# prototype2-whole-through-usb.net
KiCad netlist of a schematic drawn in EAGLE
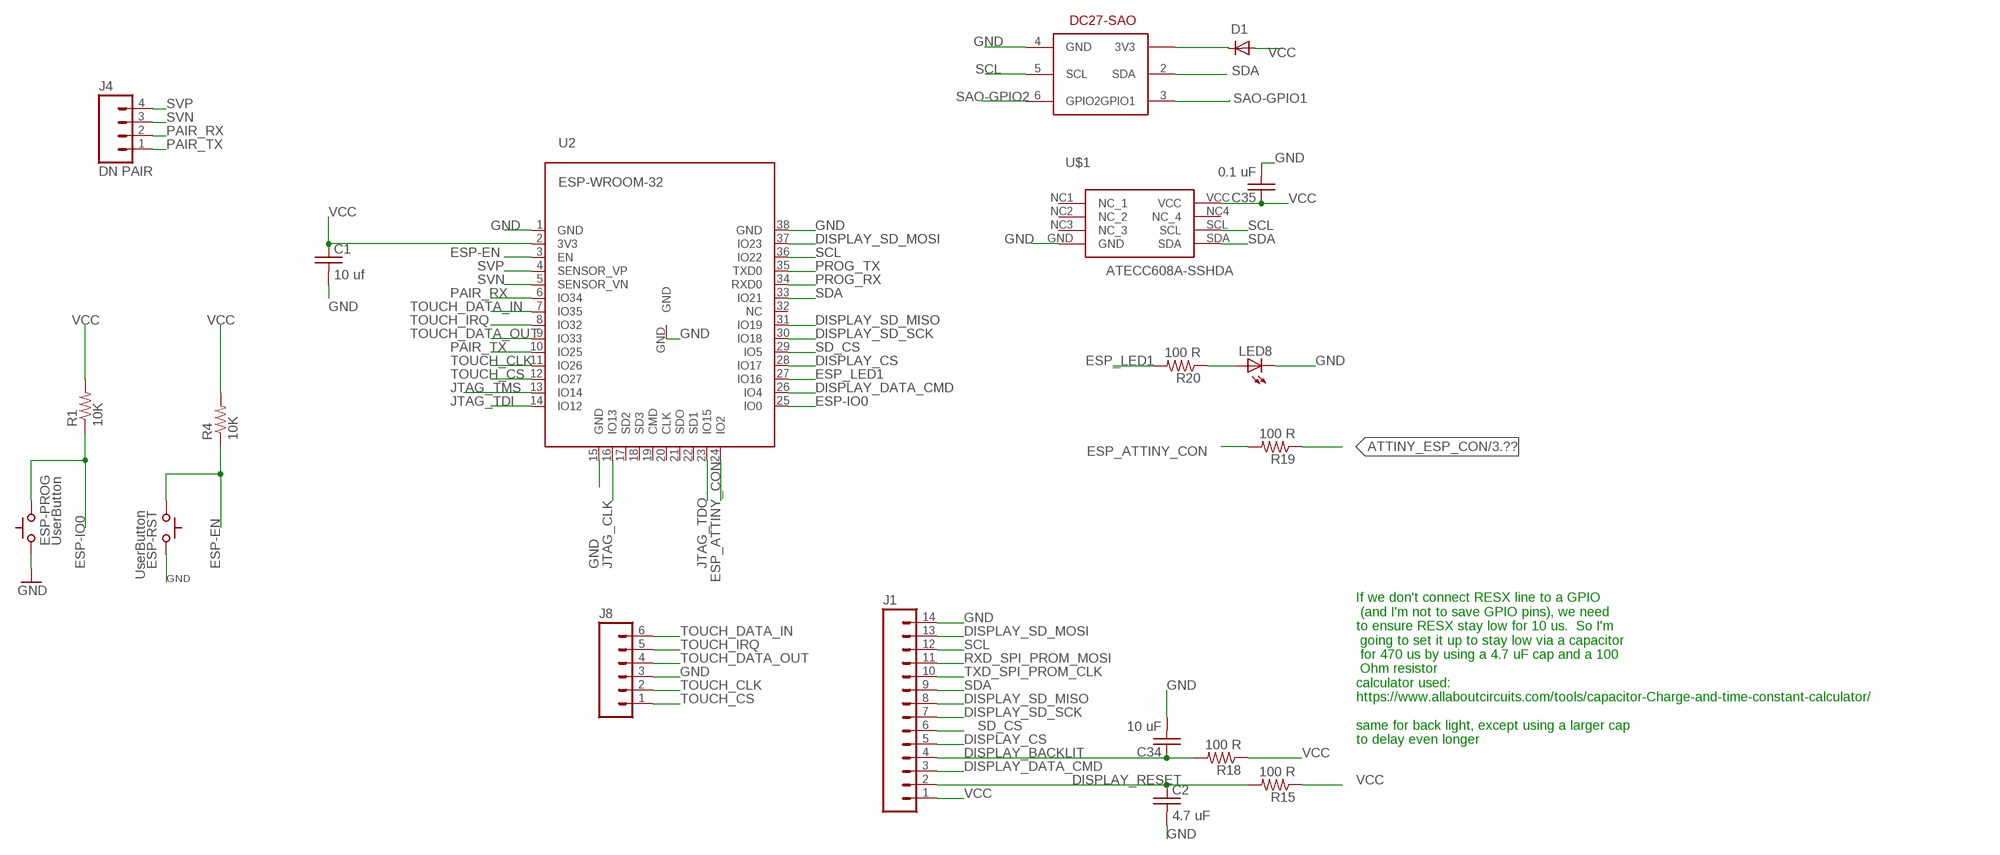
[diagram p0: schematic, sheet 1]
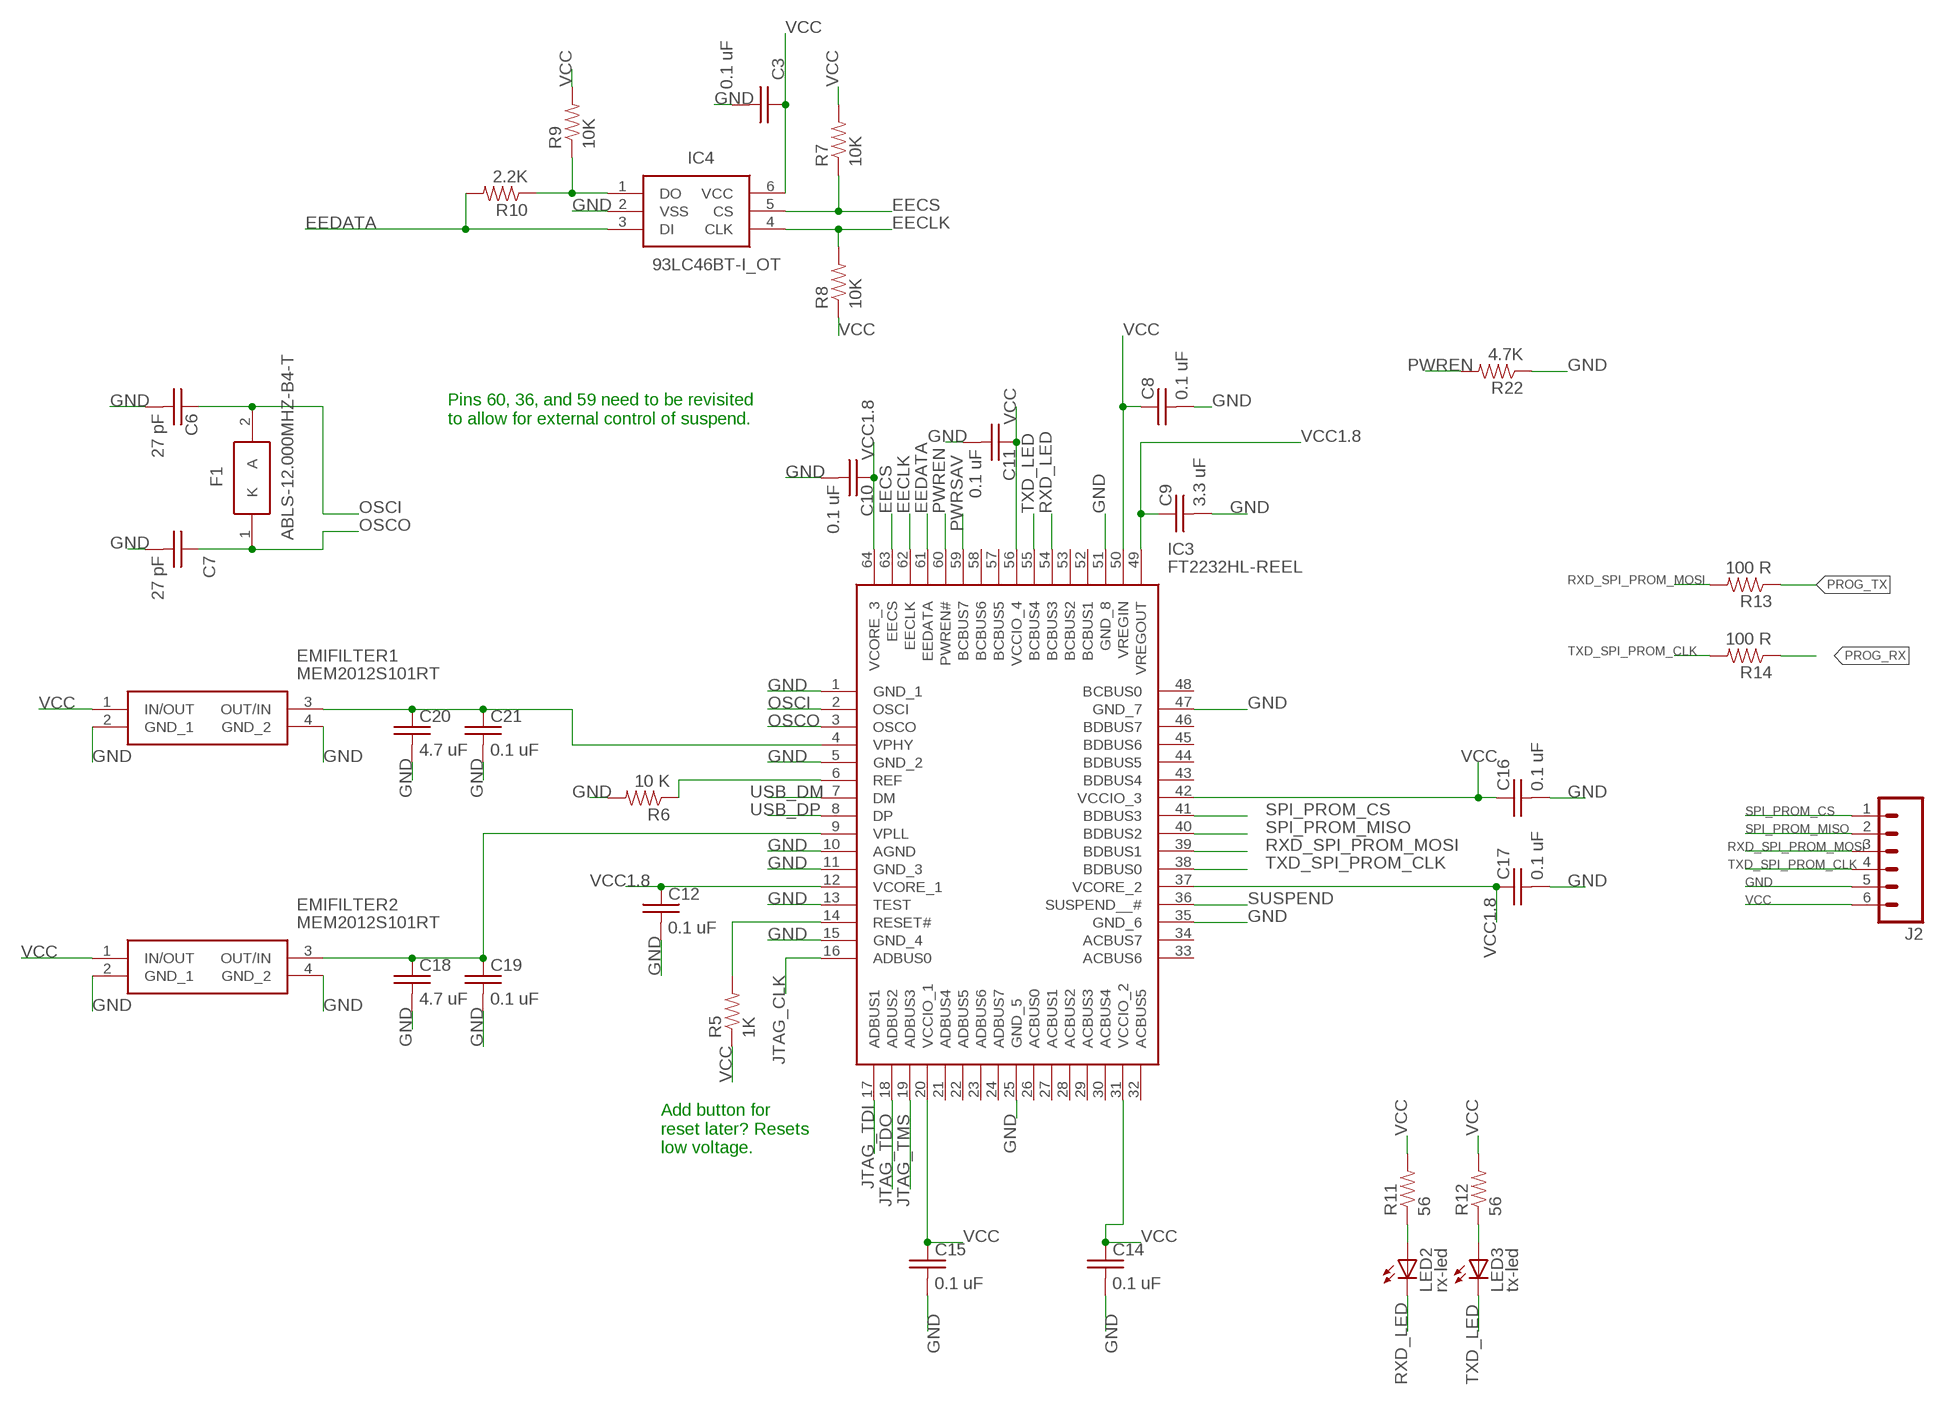
[diagram p1: schematic, sheet 2]
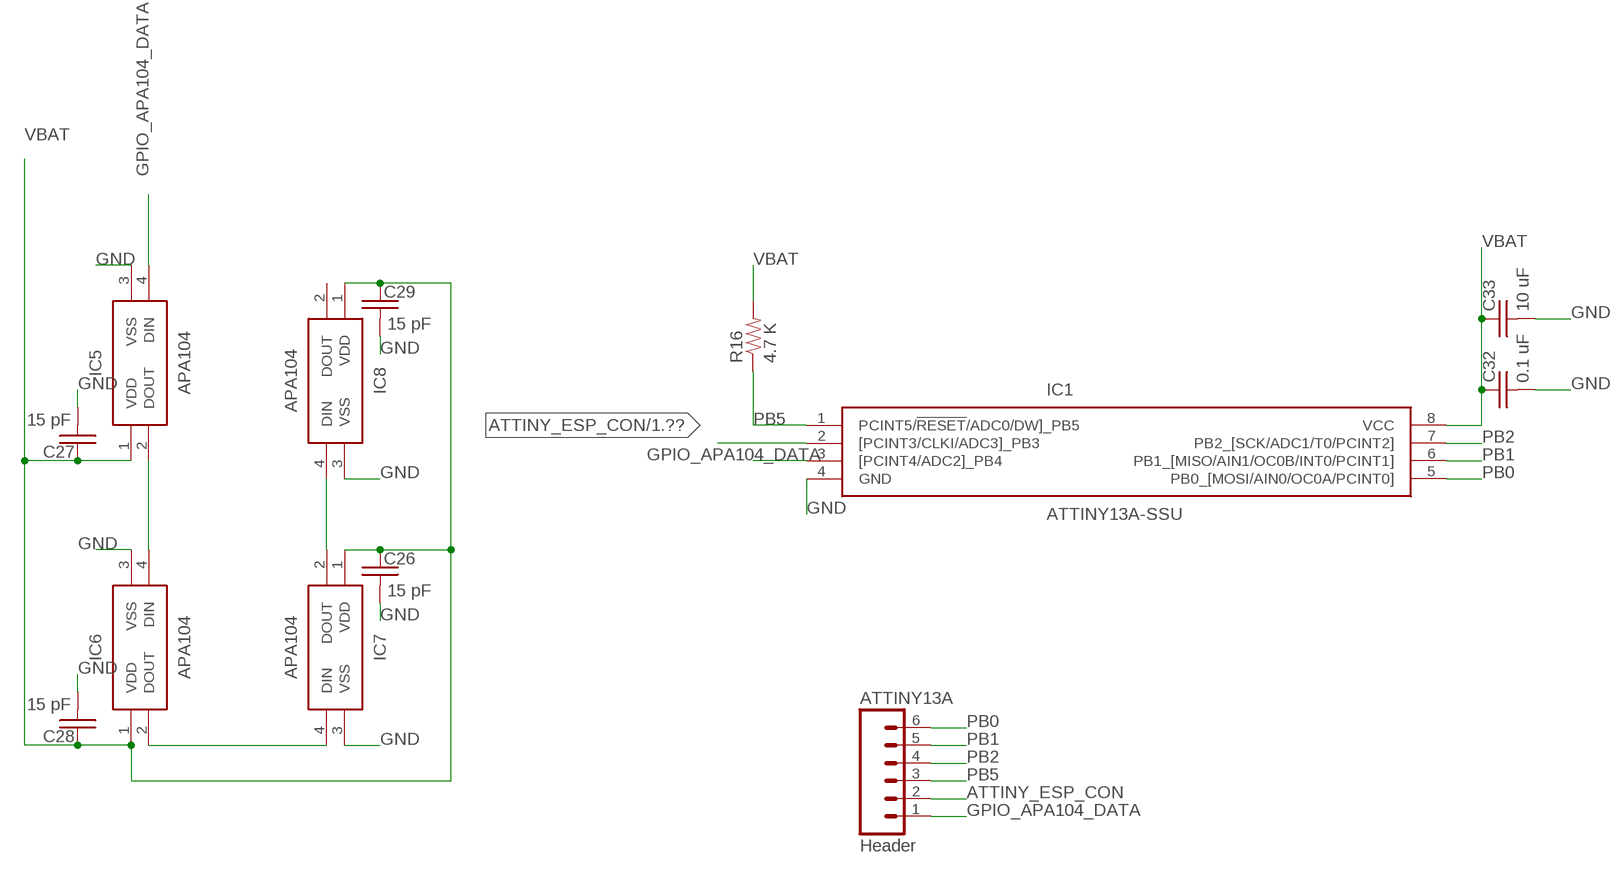
[diagram p2: schematic, sheet 3]
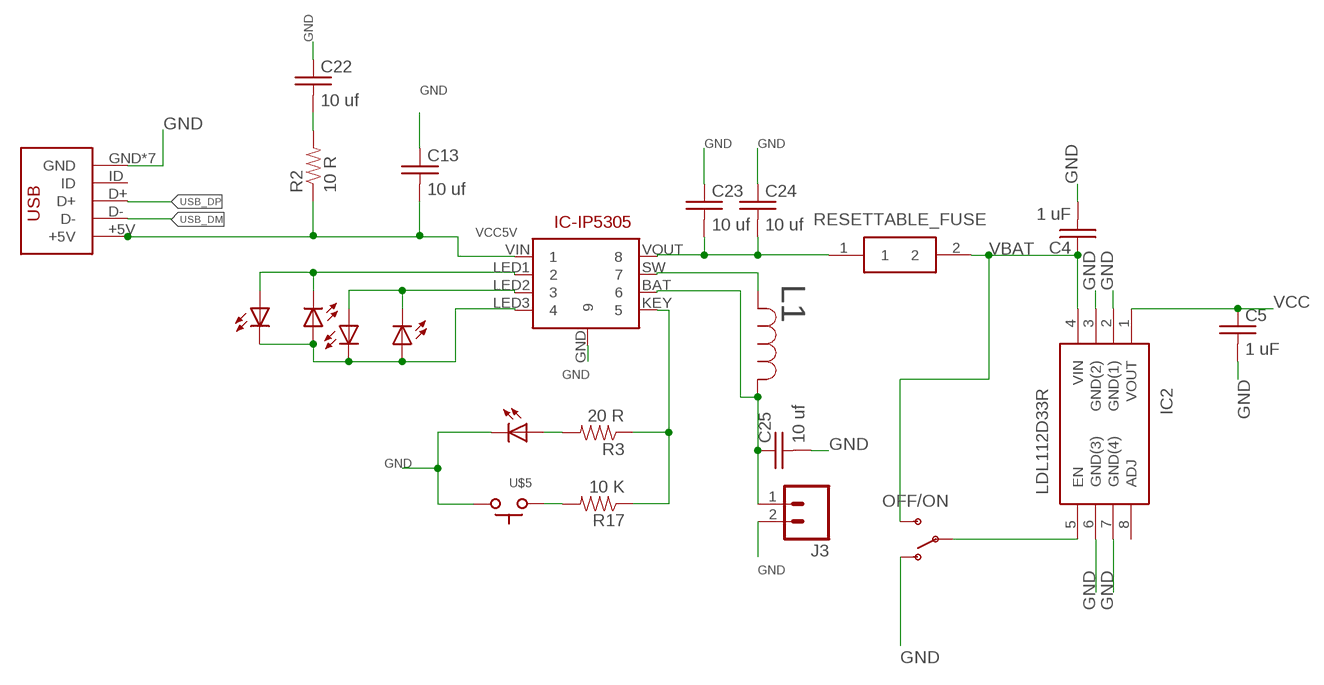
[diagram p3: schematic, sheet 4]
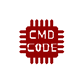
[diagram p4: schematic, sheet 5]

(export (version "E")
  (design (tool "Eeschema 10.0.6"))
  (components
    (comp (ref "ATTINY13A")
      (value "Header")
      (footprint "eagle-import:1X06")
      (libsource (lib "eagle-import") (part "M06SILK_FEMALE_PTH"))
    )
    (comp (ref "C26")
      (value "15 pF")
      (footprint "eagle-import:C0805")
      (libsource (lib "eagle-import") (part "C-USC0805"))
    )
    (comp (ref "C27")
      (value "15 pF")
      (footprint "eagle-import:C0805")
      (libsource (lib "eagle-import") (part "C-USC0805"))
    )
    (comp (ref "C28")
      (value "15 pF")
      (footprint "eagle-import:C0805")
      (libsource (lib "eagle-import") (part "C-USC0805"))
    )
    (comp (ref "C29")
      (value "15 pF")
      (footprint "eagle-import:C0805")
      (libsource (lib "eagle-import") (part "C-USC0805"))
    )
    (comp (ref "C32")
      (value "0.1 uF")
      (footprint "eagle-import:C0805")
      (libsource (lib "eagle-import") (part "C-USC0805"))
    )
    (comp (ref "C33")
      (value "10 uF")
      (footprint "eagle-import:C0805")
      (libsource (lib "eagle-import") (part "C-USC0805"))
    )
    (comp (ref "IC1")
      (value "ATTINY13A-SSU")
      (footprint "eagle-import:SOIC127P600X175-8N")
      (fields (field (name "MOUSER_PART_NUMBER") "556-ATTINY13A-SSU"))
      (libsource (lib "eagle-import") (part "ATTINY13A-SSU"))
    )
    (comp (ref "IC5")
      (value "APA104")
      (footprint "eagle-import:APA104")
      (libsource (lib "eagle-import") (part "APA104"))
    )
    (comp (ref "IC6")
      (value "APA104")
      (footprint "eagle-import:APA104")
      (libsource (lib "eagle-import") (part "APA104"))
    )
    (comp (ref "IC7")
      (value "APA104")
      (footprint "eagle-import:APA104")
      (libsource (lib "eagle-import") (part "APA104"))
    )
    (comp (ref "IC8")
      (value "APA104")
      (footprint "eagle-import:APA104")
      (libsource (lib "eagle-import") (part "APA104"))
    )
    (comp (ref "R16")
      (value "4.7 K")
      (footprint "eagle-import:0805")
      (libsource (lib "eagle-import") (part "passives_RESISTOR0805-RES"))
    )
    (comp (ref "C1")
      (value "10 uf")
      (footprint "eagle-import:C0805")
      (libsource (lib "eagle-import") (part "C-USC0805"))
    )
    (comp (ref "C2")
      (value "4.7 uF")
      (footprint "eagle-import:C0805")
      (libsource (lib "eagle-import") (part "C-USC0805"))
    )
    (comp (ref "C34")
      (value "10 uF")
      (footprint "eagle-import:C0805")
      (libsource (lib "eagle-import") (part "C-USC0805"))
    )
    (comp (ref "C35")
      (value "0.1 uF")
      (footprint "eagle-import:C0805")
      (libsource (lib "eagle-import") (part "C-USC0805"))
    )
    (comp (ref "D1")
      (value "DIODESMA")
      (footprint "eagle-import:SMA-DIODE")
      (libsource (lib "eagle-import") (part "DIODESMA"))
    )
    (comp (ref "ESP-PROG")
      (value "UserButton")
      (footprint "eagle-import:TACTILE-2PIN-NARROW")
      (libsource (lib "eagle-import") (part "SWITCH_TACTILETACTILE-2PIN-NARROW"))
    )
    (comp (ref "ESP-RST")
      (value "UserButton")
      (footprint "eagle-import:TACTILE-2PIN-NARROW")
      (libsource (lib "eagle-import") (part "SWITCH_TACTILETACTILE-2PIN-NARROW"))
    )
    (comp (ref "J1")
      (value "M14")
      (footprint "eagle-import:1X14")
      (libsource (lib "eagle-import") (part "M14"))
    )
    (comp (ref "J4")
      (value "DN PAIR")
      (footprint "eagle-import:1X04")
      (libsource (lib "eagle-import") (part "M04PTH"))
    )
    (comp (ref "J8")
      (value "M06NO_SILK_YES_STOP")
      (footprint "eagle-import:1X06_NO_SILK_YES_STOP")
      (libsource (lib "eagle-import") (part "M06NO_SILK_YES_STOP"))
    )
    (comp (ref "LED8")
      (value "LED3MM")
      (footprint "eagle-import:LED3MM")
      (libsource (lib "eagle-import") (part "LED3MM"))
    )
    (comp (ref "R1")
      (value "10K")
      (footprint "eagle-import:0805")
      (libsource (lib "eagle-import") (part "RESISTOR0805-RES"))
    )
    (comp (ref "R4")
      (value "10K")
      (footprint "eagle-import:0805")
      (libsource (lib "eagle-import") (part "RESISTOR0805-RES"))
    )
    (comp (ref "R15")
      (value "100 R")
      (footprint "eagle-import:0805")
      (libsource (lib "eagle-import") (part "RESISTOR0805-RES"))
    )
    (comp (ref "R18")
      (value "100 R")
      (footprint "eagle-import:0805")
      (libsource (lib "eagle-import") (part "RESISTOR0805-RES"))
    )
    (comp (ref "R19")
      (value "100 R")
      (footprint "eagle-import:0805")
      (libsource (lib "eagle-import") (part "RESISTOR0805-RES"))
    )
    (comp (ref "R20")
      (value "100 R")
      (footprint "eagle-import:0805")
      (libsource (lib "eagle-import") (part "RESISTOR0805-RES"))
    )
    (comp (ref "U$1")
      (value "ATECC608A-SSHDA")
      (footprint "eagle-import:8-SOIC")
      (libsource (lib "eagle-import") (part "ATECC608A-SSHDA"))
    )
    (comp (ref "U$4")
      (value "DC-27-SAO")
      (footprint "eagle-import:3X2")
      (libsource (lib "eagle-import") (part "DC-27-SAO"))
    )
    (comp (ref "U2")
      (value "ESP-WROOM-32")
      (footprint "eagle-import:ESP-WROOM-32")
      (libsource (lib "eagle-import") (part "ESP-WROOM-32"))
    )
    (comp (ref "C3")
      (value "0.1 uF")
      (footprint "eagle-import:C0805")
      (libsource (lib "eagle-import") (part "C-USC0805"))
    )
    (comp (ref "C6")
      (value "27 pF")
      (footprint "eagle-import:C0805")
      (libsource (lib "eagle-import") (part "C-USC0805"))
    )
    (comp (ref "C7")
      (value "27 pF")
      (footprint "eagle-import:C0805")
      (libsource (lib "eagle-import") (part "C-USC0805"))
    )
    (comp (ref "C8")
      (value "0.1 uF")
      (footprint "eagle-import:C0805")
      (libsource (lib "eagle-import") (part "C-USC0805"))
    )
    (comp (ref "C9")
      (value "3.3 uF")
      (footprint "eagle-import:C0805")
      (libsource (lib "eagle-import") (part "C-USC0805"))
    )
    (comp (ref "C10")
      (value "0.1 uF")
      (footprint "eagle-import:C0805")
      (libsource (lib "eagle-import") (part "C-USC0805"))
    )
    (comp (ref "C11")
      (value "0.1 uF")
      (footprint "eagle-import:C0805")
      (libsource (lib "eagle-import") (part "C-USC0805"))
    )
    (comp (ref "C12")
      (value "0.1 uF")
      (footprint "eagle-import:C0805")
      (libsource (lib "eagle-import") (part "C-USC0805"))
    )
    (comp (ref "C14")
      (value "0.1 uF")
      (footprint "eagle-import:C0805")
      (libsource (lib "eagle-import") (part "C-USC0805"))
    )
    (comp (ref "C15")
      (value "0.1 uF")
      (footprint "eagle-import:C0805")
      (libsource (lib "eagle-import") (part "C-USC0805"))
    )
    (comp (ref "C16")
      (value "0.1 uF")
      (footprint "eagle-import:C0805")
      (libsource (lib "eagle-import") (part "C-USC0805"))
    )
    (comp (ref "C17")
      (value "0.1 uF")
      (footprint "eagle-import:C0805")
      (libsource (lib "eagle-import") (part "C-USC0805"))
    )
    (comp (ref "C18")
      (value "4.7 uF")
      (footprint "eagle-import:C0805")
      (libsource (lib "eagle-import") (part "C-USC0805"))
    )
    (comp (ref "C19")
      (value "0.1 uF")
      (footprint "eagle-import:C0805")
      (libsource (lib "eagle-import") (part "C-USC0805"))
    )
    (comp (ref "C20")
      (value "4.7 uF")
      (footprint "eagle-import:C0805")
      (libsource (lib "eagle-import") (part "C-USC0805"))
    )
    (comp (ref "C21")
      (value "0.1 uF")
      (footprint "eagle-import:C0805")
      (libsource (lib "eagle-import") (part "C-USC0805"))
    )
    (comp (ref "EMIFILTER1")
      (value "MEM2012S101RT")
      (footprint "eagle-import:MEM2012S101RT")
      (libsource (lib "eagle-import") (part "MEM2012S101RT"))
    )
    (comp (ref "EMIFILTER2")
      (value "MEM2012S101RT")
      (footprint "eagle-import:MEM2012S101RT")
      (libsource (lib "eagle-import") (part "MEM2012S101RT"))
    )
    (comp (ref "F1")
      (value "ABLS-12.000MHZ-B4-T")
      (footprint "eagle-import:HC_49US-(AT49)_1")
      (fields
        (field (name "MOUSER_PART_NUMBER") "815-ABLS-12.0M-T")
        (field (name "RS_PART_NUMBER") "1710207")
      )
      (libsource (lib "eagle-import") (part "ABLS-12.000MHZ-B4-T"))
    )
    (comp (ref "IC3")
      (value "FT2232HL-REEL")
      (footprint "eagle-import:QFP50P1200X1200X160-64N")
      (fields (field (name "MOUSER_PART_NUMBER") "895-FT2232HL"))
      (libsource (lib "eagle-import") (part "FT2232HL-REEL"))
    )
    (comp (ref "IC4")
      (value "93LC46BT-I_OT")
      (footprint "eagle-import:SOT95P270X145-6N")
      (fields
        (field (name "MANUFACTURER_PART_NUMBER") "93LC46BT-I/OT")
        (field (name "MOUSER_PART_NUMBER") "579-93LC46BT-I/OT")
      )
      (libsource (lib "eagle-import") (part "93LC46BT-I_OT"))
    )
    (comp (ref "J2")
      (value "M06SILK_FEMALE_PTH")
      (footprint "eagle-import:1X06")
      (libsource (lib "eagle-import") (part "M06SILK_FEMALE_PTH"))
    )
    (comp (ref "LED2")
      (value "rx-led")
      (footprint "eagle-import:LED3MM")
      (libsource (lib "eagle-import") (part "LED3MM"))
    )
    (comp (ref "LED3")
      (value "tx-led")
      (footprint "eagle-import:LED3MM")
      (libsource (lib "eagle-import") (part "LED3MM"))
    )
    (comp (ref "R5")
      (value "1K")
      (footprint "eagle-import:0805")
      (libsource (lib "eagle-import") (part "passives_RESISTOR0805-RES"))
    )
    (comp (ref "R6")
      (value "10 K")
      (footprint "eagle-import:0805")
      (libsource (lib "eagle-import") (part "passives_RESISTOR0805-RES"))
    )
    (comp (ref "R7")
      (value "10K")
      (footprint "eagle-import:0805")
      (libsource (lib "eagle-import") (part "passives_RESISTOR0805-RES"))
    )
    (comp (ref "R8")
      (value "10K")
      (footprint "eagle-import:0805")
      (libsource (lib "eagle-import") (part "passives_RESISTOR0805-RES"))
    )
    (comp (ref "R9")
      (value "10K")
      (footprint "eagle-import:0805")
      (libsource (lib "eagle-import") (part "passives_RESISTOR0805-RES"))
    )
    (comp (ref "R10")
      (value "2.2K")
      (footprint "eagle-import:0805")
      (libsource (lib "eagle-import") (part "passives_RESISTOR0805-RES"))
    )
    (comp (ref "R11")
      (value "56")
      (footprint "eagle-import:0805")
      (libsource (lib "eagle-import") (part "passives_RESISTOR0805-RES"))
    )
    (comp (ref "R12")
      (value "56")
      (footprint "eagle-import:0805")
      (libsource (lib "eagle-import") (part "passives_RESISTOR0805-RES"))
    )
    (comp (ref "R13")
      (value "100 R")
      (footprint "eagle-import:0805")
      (libsource (lib "eagle-import") (part "passives_RESISTOR0805-RES"))
    )
    (comp (ref "R14")
      (value "100 R")
      (footprint "eagle-import:0805")
      (libsource (lib "eagle-import") (part "passives_RESISTOR0805-RES"))
    )
    (comp (ref "R22")
      (value "4.7K")
      (footprint "eagle-import:0805")
      (libsource (lib "eagle-import") (part "passives_RESISTOR0805-RES"))
    )
    (comp (ref "C4")
      (value "1 uF")
      (footprint "eagle-import:C0805")
      (libsource (lib "eagle-import") (part "C-USC0805"))
    )
    (comp (ref "C5")
      (value "1 uF")
      (footprint "eagle-import:C0805")
      (libsource (lib "eagle-import") (part "C-USC0805"))
    )
    (comp (ref "C13")
      (value "10 uf")
      (footprint "eagle-import:C0805")
      (libsource (lib "eagle-import") (part "C-USC0805"))
    )
    (comp (ref "C22")
      (value "10 uf")
      (footprint "eagle-import:C0805")
      (libsource (lib "eagle-import") (part "C-USC0805"))
    )
    (comp (ref "C23")
      (value "10 uf")
      (footprint "eagle-import:C0805")
      (libsource (lib "eagle-import") (part "C-USC0805"))
    )
    (comp (ref "C24")
      (value "10 uf")
      (footprint "eagle-import:C0805")
      (libsource (lib "eagle-import") (part "C-USC0805"))
    )
    (comp (ref "C25")
      (value "10 uf")
      (footprint "eagle-import:C0805")
      (libsource (lib "eagle-import") (part "C-USC0805"))
    )
    (comp (ref "IC-IP5305")
      (value "IP5305ESOP8")
      (footprint "eagle-import:SOIC127P600X165-8")
      (libsource (lib "eagle-import") (part "IP5305ESOP8"))
    )
    (comp (ref "IC2")
      (value "LDL112D33R")
      (footprint "eagle-import:SOIC127P600X175-8N")
      (libsource (lib "eagle-import") (part "LDL112D33R"))
    )
    (comp (ref "J3")
      (value "M02PTH")
      (footprint "eagle-import:1X02")
      (libsource (lib "eagle-import") (part "M02PTH"))
    )
    (comp (ref "L1")
      (value "NRS4018T2R2MDGJ")
      (footprint "eagle-import:IND_TAIYO_NRS4018")
      (libsource (lib "eagle-import") (part "NRS4018T2R2MDGJ"))
    )
    (comp (ref "LED1")
      (value "LED3MM")
      (footprint "eagle-import:LED3MM")
      (libsource (lib "eagle-import") (part "LED3MM"))
    )
    (comp (ref "LED4")
      (value "LED3MM")
      (footprint "eagle-import:LED3MM")
      (libsource (lib "eagle-import") (part "LED3MM"))
    )
    (comp (ref "LED5")
      (value "LED3MM")
      (footprint "eagle-import:LED3MM")
      (libsource (lib "eagle-import") (part "LED3MM"))
    )
    (comp (ref "LED6")
      (value "LED3MM")
      (footprint "eagle-import:LED3MM")
      (libsource (lib "eagle-import") (part "LED3MM"))
    )
    (comp (ref "LED7")
      (value "LED3MM")
      (footprint "eagle-import:LED3MM")
      (libsource (lib "eagle-import") (part "LED3MM"))
    )
    (comp (ref "OFF/ON")
      (value "SWITCH-SPSTKIT")
      (footprint "eagle-import:SWITCH-SPDT_KIT")
      (libsource (lib "eagle-import") (part "SWITCH-SPSTKIT"))
    )
    (comp (ref "R2")
      (value "10 R")
      (footprint "eagle-import:0805")
      (libsource (lib "eagle-import") (part "passives_RESISTOR0805-RES"))
    )
    (comp (ref "R3")
      (value "20 R")
      (footprint "eagle-import:0805")
      (libsource (lib "eagle-import") (part "passives_RESISTOR0805-RES"))
    )
    (comp (ref "R17")
      (value "10 K")
      (footprint "eagle-import:0805")
      (libsource (lib "eagle-import") (part "passives_RESISTOR0805-RES"))
    )
    (comp (ref "RESETTABLE_FUSE")
      (value "0ZCJ0050FF2G")
      (footprint "eagle-import:FUSC3216X55N")
      (libsource (lib "eagle-import") (part "0ZCJ0050FF2G"))
    )
    (comp (ref "U$2")
      (value "DX4R005JJ2DX4R005JJ2")
      (footprint "eagle-import:DX4R005JJ2")
      (libsource (lib "eagle-import") (part "DX4R005JJ2DX4R005JJ2"))
    )
    (comp (ref "U$5")
      (value "SWITCH_TACTILETACTILE-2PIN-NARROW")
      (footprint "eagle-import:TACTILE-2PIN-NARROW")
      (libsource (lib "eagle-import") (part "switches_SWITCH_TACTILETACTILE-2PIN-NARROW"))
    )
    (comp (ref "U$3")
      (value "CMD_C0DE_LOGOCMD_CODE_LOGO_TOP_COPPER")
      (footprint "eagle-import:CMD_C0DE_LOGO_TOP_COPPER")
      (libsource (lib "eagle-import") (part "CMD_C0DE_LOGOCMD_CODE_LOGO_TOP_COPPER"))
    )
  )
  (nets
    (net (code "1") (name "ATTINY_ESP_CON") (class "Default")
      (node (ref "ATTINY13A") (pin "2") (pinfunction "2_2") (pintype "passive"))
      (node (ref "IC1") (pin "2") (pinfunction "[PCINT3/CLKI/ADC3]_PB3_2") (pintype "input"))
      (node (ref "R19") (pin "1") (pinfunction "1_1") (pintype "passive"))
    )
    (net (code "2") (name "DISPLAY_BACKLIT") (class "Default")
      (node (ref "C34") (pin "1") (pinfunction "1_1") (pintype "passive"))
      (node (ref "J1") (pin "4") (pinfunction "4_4") (pintype "passive"))
      (node (ref "R18") (pin "2") (pinfunction "2_2") (pintype "passive"))
    )
    (net (code "3") (name "DISPLAY_CS") (class "Default")
      (node (ref "J1") (pin "5") (pinfunction "5_5") (pintype "passive"))
      (node (ref "U2") (pin "28") (pinfunction "IO17_28") (pintype "bidirectional"))
    )
    (net (code "4") (name "DISPLAY_DATA_CMD") (class "Default")
      (node (ref "J1") (pin "3") (pinfunction "3_3") (pintype "passive"))
      (node (ref "U2") (pin "26") (pinfunction "IO4_26") (pintype "bidirectional"))
    )
    (net (code "5") (name "DISPLAY_RESET") (class "Default")
      (node (ref "C2") (pin "1") (pinfunction "1_1") (pintype "passive"))
      (node (ref "J1") (pin "2") (pinfunction "2_2") (pintype "passive"))
      (node (ref "R15") (pin "2") (pinfunction "2_2") (pintype "passive"))
    )
    (net (code "6") (name "DISPLAY_SD_MISO") (class "Default")
      (node (ref "J1") (pin "8") (pinfunction "8_8") (pintype "passive"))
      (node (ref "U2") (pin "31") (pinfunction "IO19_31") (pintype "bidirectional"))
    )
    (net (code "7") (name "DISPLAY_SD_MOSI") (class "Default")
      (node (ref "J1") (pin "13") (pinfunction "13_13") (pintype "passive"))
      (node (ref "U2") (pin "37") (pinfunction "IO23_37") (pintype "bidirectional"))
    )
    (net (code "8") (name "DISPLAY_SD_SCK") (class "Default")
      (node (ref "J1") (pin "7") (pinfunction "7_7") (pintype "passive"))
      (node (ref "U2") (pin "30") (pinfunction "IO18_30") (pintype "bidirectional"))
    )
    (net (code "9") (name "EECLK") (class "Default")
      (node (ref "IC3") (pin "62") (pinfunction "EECLK_62") (pintype "bidirectional"))
      (node (ref "IC4") (pin "4") (pinfunction "CLK_4") (pintype "input"))
      (node (ref "R8") (pin "2") (pinfunction "2_2") (pintype "passive"))
    )
    (net (code "10") (name "EECS") (class "Default")
      (node (ref "IC3") (pin "63") (pinfunction "EECS_63") (pintype "bidirectional"))
      (node (ref "IC4") (pin "5") (pinfunction "CS_5") (pintype "input"))
      (node (ref "R7") (pin "1") (pinfunction "1_1") (pintype "passive"))
    )
    (net (code "11") (name "EEDATA") (class "Default")
      (node (ref "IC3") (pin "61") (pinfunction "EEDATA_61") (pintype "bidirectional"))
      (node (ref "IC4") (pin "3") (pinfunction "DI_3") (pintype "bidirectional"))
      (node (ref "R10") (pin "2") (pinfunction "2_2") (pintype "passive"))
    )
    (net (code "12") (name "ESP-EN") (class "Default")
      (node (ref "ESP-RST") (pin "P$2") (pinfunction "C_P$2") (pintype "passive"))
      (node (ref "R4") (pin "1") (pinfunction "1_1") (pintype "passive"))
      (node (ref "U2") (pin "3") (pinfunction "EN_3") (pintype "bidirectional"))
    )
    (net (code "13") (name "ESP-IO0") (class "Default")
      (node (ref "ESP-PROG") (pin "P$1") (pinfunction "A_P$1") (pintype "passive"))
      (node (ref "R1") (pin "1") (pinfunction "1_1") (pintype "passive"))
      (node (ref "U2") (pin "25") (pinfunction "IO0_25") (pintype "bidirectional"))
    )
    (net (code "14") (name "ESP_ATTINY_CON") (class "Default")
      (node (ref "R19") (pin "2") (pinfunction "2_2") (pintype "passive"))
      (node (ref "U2") (pin "24") (pinfunction "IO2_24") (pintype "bidirectional"))
    )
    (net (code "15") (name "ESP_LED1") (class "Default")
      (node (ref "R20") (pin "2") (pinfunction "2_2") (pintype "passive"))
      (node (ref "U2") (pin "27") (pinfunction "IO16_27") (pintype "bidirectional"))
    )
    (net (code "16") (name "GND") (class "Default")
      (node (ref "C1") (pin "2") (pinfunction "2_2") (pintype "passive"))
      (node (ref "C10") (pin "2") (pinfunction "2_2") (pintype "passive"))
      (node (ref "C11") (pin "2") (pinfunction "2_2") (pintype "passive"))
      (node (ref "C12") (pin "2") (pinfunction "2_2") (pintype "passive"))
      (node (ref "C13") (pin "1") (pinfunction "1_1") (pintype "passive"))
      (node (ref "C14") (pin "2") (pinfunction "2_2") (pintype "passive"))
      (node (ref "C15") (pin "2") (pinfunction "2_2") (pintype "passive"))
      (node (ref "C16") (pin "2") (pinfunction "2_2") (pintype "passive"))
      (node (ref "C17") (pin "2") (pinfunction "2_2") (pintype "passive"))
      (node (ref "C18") (pin "2") (pinfunction "2_2") (pintype "passive"))
      (node (ref "C19") (pin "2") (pinfunction "2_2") (pintype "passive"))
      (node (ref "C2") (pin "2") (pinfunction "2_2") (pintype "passive"))
      (node (ref "C20") (pin "2") (pinfunction "2_2") (pintype "passive"))
      (node (ref "C21") (pin "2") (pinfunction "2_2") (pintype "passive"))
      (node (ref "C22") (pin "1") (pinfunction "1_1") (pintype "passive"))
      (node (ref "C23") (pin "1") (pinfunction "1_1") (pintype "passive"))
      (node (ref "C24") (pin "1") (pinfunction "1_1") (pintype "passive"))
      (node (ref "C25") (pin "2") (pinfunction "2_2") (pintype "passive"))
      (node (ref "C26") (pin "2") (pinfunction "2_2") (pintype "passive"))
      (node (ref "C27") (pin "2") (pinfunction "2_2") (pintype "passive"))
      (node (ref "C28") (pin "2") (pinfunction "2_2") (pintype "passive"))
      (node (ref "C29") (pin "2") (pinfunction "2_2") (pintype "passive"))
      (node (ref "C3") (pin "2") (pinfunction "2_2") (pintype "passive"))
      (node (ref "C32") (pin "2") (pinfunction "2_2") (pintype "passive"))
      (node (ref "C33") (pin "2") (pinfunction "2_2") (pintype "passive"))
      (node (ref "C34") (pin "2") (pinfunction "2_2") (pintype "passive"))
      (node (ref "C35") (pin "2") (pinfunction "2_2") (pintype "passive"))
      (node (ref "C4") (pin "2") (pinfunction "2_2") (pintype "passive"))
      (node (ref "C5") (pin "2") (pinfunction "2_2") (pintype "passive"))
      (node (ref "C6") (pin "2") (pinfunction "2_2") (pintype "passive"))
      (node (ref "C7") (pin "2") (pinfunction "2_2") (pintype "passive"))
      (node (ref "C8") (pin "2") (pinfunction "2_2") (pintype "passive"))
      (node (ref "C9") (pin "2") (pinfunction "2_2") (pintype "passive"))
      (node (ref "EMIFILTER1") (pin "2") (pinfunction "GND_1_2") (pintype "bidirectional"))
      (node (ref "EMIFILTER1") (pin "4") (pinfunction "GND_2_4") (pintype "bidirectional"))
      (node (ref "EMIFILTER2") (pin "2") (pinfunction "GND_1_2") (pintype "bidirectional"))
      (node (ref "EMIFILTER2") (pin "4") (pinfunction "GND_2_4") (pintype "bidirectional"))
      (node (ref "ESP-PROG") (pin "P$2") (pinfunction "C_P$2") (pintype "passive"))
      (node (ref "ESP-RST") (pin "P$1") (pinfunction "A_P$1") (pintype "passive"))
      (node (ref "IC-IP5305") (pin "GND") (pinfunction "9_GND") (pintype "power_in"))
      (node (ref "IC1") (pin "4") (pinfunction "GND_4") (pintype "power_in"))
      (node (ref "IC2") (pin "2") (pinfunction "GND(1)_2") (pintype "bidirectional"))
      (node (ref "IC2") (pin "3") (pinfunction "GND(2)_3") (pintype "bidirectional"))
      (node (ref "IC2") (pin "6") (pinfunction "GND(3)_6") (pintype "bidirectional"))
      (node (ref "IC2") (pin "7") (pinfunction "GND(4)_7") (pintype "bidirectional"))
      (node (ref "IC3") (pin "1") (pinfunction "GND_1_1") (pintype "bidirectional"))
      (node (ref "IC3") (pin "10") (pinfunction "AGND_10") (pintype "bidirectional"))
      (node (ref "IC3") (pin "11") (pinfunction "GND_3_11") (pintype "bidirectional"))
      (node (ref "IC3") (pin "13") (pinfunction "TEST_13") (pintype "bidirectional"))
      (node (ref "IC3") (pin "15") (pinfunction "GND_4_15") (pintype "bidirectional"))
      (node (ref "IC3") (pin "25") (pinfunction "GND_5_25") (pintype "bidirectional"))
      (node (ref "IC3") (pin "35") (pinfunction "GND_6_35") (pintype "bidirectional"))
      (node (ref "IC3") (pin "47") (pinfunction "GND_7_47") (pintype "bidirectional"))
      (node (ref "IC3") (pin "5") (pinfunction "GND_2_5") (pintype "bidirectional"))
      (node (ref "IC3") (pin "51") (pinfunction "GND_8_51") (pintype "bidirectional"))
      (node (ref "IC4") (pin "2") (pinfunction "VSS_2") (pintype "power_in"))
      (node (ref "IC5") (pin "3") (pinfunction "VSS_3") (pintype "power_in"))
      (node (ref "IC6") (pin "3") (pinfunction "VSS_3") (pintype "power_in"))
      (node (ref "IC7") (pin "3") (pinfunction "VSS_3") (pintype "power_in"))
      (node (ref "IC8") (pin "3") (pinfunction "VSS_3") (pintype "power_in"))
      (node (ref "J1") (pin "14") (pinfunction "14_14") (pintype "passive"))
      (node (ref "J2") (pin "5") (pinfunction "5_5") (pintype "passive"))
      (node (ref "J3") (pin "2") (pinfunction "2_2") (pintype "passive"))
      (node (ref "J8") (pin "3") (pinfunction "3_3") (pintype "passive"))
      (node (ref "LED7") (pin "K") (pinfunction "C_K") (pintype "output"))
      (node (ref "LED8") (pin "K") (pinfunction "C_K") (pintype "output"))
      (node (ref "OFF/ON") (pin "1") (pinfunction "O_1") (pintype "passive"))
      (node (ref "R22") (pin "1") (pinfunction "1_1") (pintype "passive"))
      (node (ref "R6") (pin "2") (pinfunction "2_2") (pintype "passive"))
      (node (ref "U$1") (pin "GND") (pinfunction "GND_GND") (pintype "power_in"))
      (node (ref "U$2") (pin "GND") (pinfunction "GND_GND") (pintype "bidirectional"))
      (node (ref "U$2") (pin "P$10") (pinfunction "GND_P$10") (pintype "bidirectional"))
      (node (ref "U$2") (pin "P$11") (pinfunction "GND_P$11") (pintype "bidirectional"))
      (node (ref "U$2") (pin "P$6") (pinfunction "GND_P$6") (pintype "bidirectional"))
      (node (ref "U$2") (pin "P$7") (pinfunction "GND_P$7") (pintype "bidirectional"))
      (node (ref "U$2") (pin "P$8") (pinfunction "GND_P$8") (pintype "bidirectional"))
      (node (ref "U$2") (pin "P$9") (pinfunction "GND_P$9") (pintype "bidirectional"))
      (node (ref "U$4") (pin "4") (pinfunction "GND_4") (pintype "power_in"))
      (node (ref "U$5") (pin "P$1") (pinfunction "A_P$1") (pintype "passive"))
      (node (ref "U2") (pin "1") (pinfunction "GND_1") (pintype "bidirectional"))
      (node (ref "U2") (pin "15") (pinfunction "GND_15") (pintype "bidirectional"))
      (node (ref "U2") (pin "38") (pinfunction "GND_38") (pintype "bidirectional"))
      (node (ref "U2") (pin "GND") (pinfunction "GND_GND") (pintype "bidirectional"))
    )
    (net (code "17") (name "GPIO_APA104_DATA") (class "Default")
      (node (ref "ATTINY13A") (pin "1") (pinfunction "1_1") (pintype "passive"))
      (node (ref "IC1") (pin "3") (pinfunction "[PCINT4/ADC2]_PB4_3") (pintype "input"))
      (node (ref "IC5") (pin "4") (pinfunction "DIN_4") (pintype "input"))
    )
    (net (code "18") (name "JTAG_CLK") (class "Default")
      (node (ref "IC3") (pin "16") (pinfunction "ADBUS0_16") (pintype "bidirectional"))
      (node (ref "U2") (pin "16") (pinfunction "IO13_16") (pintype "bidirectional"))
    )
    (net (code "19") (name "JTAG_TDI") (class "Default")
      (node (ref "IC3") (pin "17") (pinfunction "ADBUS1_17") (pintype "bidirectional"))
      (node (ref "U2") (pin "14") (pinfunction "IO12_14") (pintype "bidirectional"))
    )
    (net (code "20") (name "JTAG_TDO") (class "Default")
      (node (ref "IC3") (pin "18") (pinfunction "ADBUS2_18") (pintype "bidirectional"))
      (node (ref "U2") (pin "23") (pinfunction "IO15_23") (pintype "bidirectional"))
    )
    (net (code "21") (name "JTAG_TMS") (class "Default")
      (node (ref "IC3") (pin "19") (pinfunction "ADBUS3_19") (pintype "bidirectional"))
      (node (ref "U2") (pin "13") (pinfunction "IO14_13") (pintype "bidirectional"))
    )
    (net (code "22") (name "Net-(C22-Pad2)") (class "Default")
      (node (ref "C22") (pin "2") (pinfunction "2_2") (pintype "passive"))
      (node (ref "R2") (pin "2") (pinfunction "2_2") (pintype "passive"))
    )
    (net (code "23") (name "Net-(EMIFILTER1-OUT{slash}IN)") (class "Default")
      (node (ref "C20") (pin "1") (pinfunction "1_1") (pintype "passive"))
      (node (ref "C21") (pin "1") (pinfunction "1_1") (pintype "passive"))
      (node (ref "EMIFILTER1") (pin "3") (pinfunction "OUT/IN_3") (pintype "bidirectional"))
      (node (ref "IC3") (pin "4") (pinfunction "VPHY_4") (pintype "bidirectional"))
    )
    (net (code "24") (name "Net-(EMIFILTER2-OUT{slash}IN)") (class "Default")
      (node (ref "C18") (pin "1") (pinfunction "1_1") (pintype "passive"))
      (node (ref "C19") (pin "1") (pinfunction "1_1") (pintype "passive"))
      (node (ref "EMIFILTER2") (pin "3") (pinfunction "OUT/IN_3") (pintype "bidirectional"))
      (node (ref "IC3") (pin "9") (pinfunction "VPLL_9") (pintype "bidirectional"))
    )
    (net (code "25") (name "Net-(IC-IP5305-2)") (class "Default")
      (node (ref "IC-IP5305") (pin "LED1") (pinfunction "2_LED1") (pintype "output"))
      (node (ref "LED1") (pin "A") (pinfunction "A_A") (pintype "input"))
      (node (ref "LED4") (pin "K") (pinfunction "C_K") (pintype "output"))
    )
    (net (code "26") (name "Net-(IC-IP5305-3)") (class "Default")
      (node (ref "IC-IP5305") (pin "LED2") (pinfunction "3_LED2") (pintype "output"))
      (node (ref "LED5") (pin "A") (pinfunction "A_A") (pintype "input"))
      (node (ref "LED6") (pin "K") (pinfunction "C_K") (pintype "output"))
    )
    (net (code "27") (name "Net-(IC-IP5305-4)") (class "Default")
      (node (ref "IC-IP5305") (pin "LED3") (pinfunction "4_LED3") (pintype "output"))
      (node (ref "LED1") (pin "K") (pinfunction "C_K") (pintype "output"))
      (node (ref "LED4") (pin "A") (pinfunction "A_A") (pintype "input"))
      (node (ref "LED5") (pin "K") (pinfunction "C_K") (pintype "output"))
      (node (ref "LED6") (pin "A") (pinfunction "A_A") (pintype "input"))
    )
    (net (code "28") (name "Net-(IC-IP5305-5)") (class "Default")
      (node (ref "IC-IP5305") (pin "KEY") (pinfunction "5_KEY") (pintype "bidirectional"))
      (node (ref "R17") (pin "1") (pinfunction "1_1") (pintype "passive"))
      (node (ref "R3") (pin "1") (pinfunction "1_1") (pintype "passive"))
    )
    (net (code "29") (name "Net-(IC-IP5305-6)") (class "Default")
      (node (ref "C25") (pin "1") (pinfunction "1_1") (pintype "passive"))
      (node (ref "IC-IP5305") (pin "BAT") (pinfunction "6_BAT") (pintype "bidirectional"))
      (node (ref "J3") (pin "1") (pinfunction "1_1") (pintype "passive"))
      (node (ref "L1") (pin "1") (pinfunction "1_1") (pintype "passive"))
    )
    (net (code "30") (name "Net-(IC-IP5305-7)") (class "Default")
      (node (ref "IC-IP5305") (pin "SW") (pinfunction "7_SW") (pintype "bidirectional"))
      (node (ref "L1") (pin "2") (pinfunction "2_2") (pintype "passive"))
    )
    (net (code "31") (name "Net-(IC-IP5305-8)") (class "Default")
      (node (ref "C23") (pin "2") (pinfunction "2_2") (pintype "passive"))
      (node (ref "C24") (pin "2") (pinfunction "2_2") (pintype "passive"))
      (node (ref "IC-IP5305") (pin "VOUT") (pinfunction "8_VOUT") (pintype "bidirectional"))
      (node (ref "RESETTABLE_FUSE") (pin "1") (pinfunction "1_1") (pintype "passive"))
    )
    (net (code "32") (name "Net-(IC2-EN)") (class "Default")
      (node (ref "IC2") (pin "5") (pinfunction "EN_5") (pintype "bidirectional"))
      (node (ref "OFF/ON") (pin "2") (pinfunction "P_2") (pintype "passive"))
    )
    (net (code "33") (name "Net-(IC3-REF)") (class "Default")
      (node (ref "IC3") (pin "6") (pinfunction "REF_6") (pintype "bidirectional"))
      (node (ref "R6") (pin "1") (pinfunction "1_1") (pintype "passive"))
    )
    (net (code "34") (name "Net-(IC3-RESET#)") (class "Default")
      (node (ref "IC3") (pin "14") (pinfunction "RESET#_14") (pintype "bidirectional"))
      (node (ref "R5") (pin "2") (pinfunction "2_2") (pintype "passive"))
    )
    (net (code "35") (name "Net-(IC4-DO)") (class "Default")
      (node (ref "IC4") (pin "1") (pinfunction "DO_1") (pintype "bidirectional"))
      (node (ref "R10") (pin "1") (pinfunction "1_1") (pintype "passive"))
      (node (ref "R9") (pin "1") (pinfunction "1_1") (pintype "passive"))
    )
    (net (code "36") (name "Net-(IC5-DOUT)") (class "Default")
      (node (ref "IC5") (pin "2") (pinfunction "DOUT_2") (pintype "output"))
      (node (ref "IC6") (pin "4") (pinfunction "DIN_4") (pintype "input"))
    )
    (net (code "37") (name "Net-(IC6-DOUT)") (class "Default")
      (node (ref "IC6") (pin "2") (pinfunction "DOUT_2") (pintype "output"))
      (node (ref "IC7") (pin "4") (pinfunction "DIN_4") (pintype "input"))
    )
    (net (code "38") (name "Net-(IC7-DOUT)") (class "Default")
      (node (ref "IC7") (pin "2") (pinfunction "DOUT_2") (pintype "output"))
      (node (ref "IC8") (pin "4") (pinfunction "DIN_4") (pintype "input"))
    )
    (net (code "39") (name "Net-(LED2-PadA)") (class "Default")
      (node (ref "LED2") (pin "A") (pinfunction "A_A") (pintype "input"))
      (node (ref "R11") (pin "1") (pinfunction "1_1") (pintype "passive"))
    )
    (net (code "40") (name "Net-(LED3-PadA)") (class "Default")
      (node (ref "LED3") (pin "A") (pinfunction "A_A") (pintype "input"))
      (node (ref "R12") (pin "1") (pinfunction "1_1") (pintype "passive"))
    )
    (net (code "41") (name "Net-(LED7-PadA)") (class "Default")
      (node (ref "LED7") (pin "A") (pinfunction "A_A") (pintype "input"))
      (node (ref "R3") (pin "2") (pinfunction "2_2") (pintype "passive"))
    )
    (net (code "42") (name "Net-(LED8-PadA)") (class "Default")
      (node (ref "LED8") (pin "A") (pinfunction "A_A") (pintype "input"))
      (node (ref "R20") (pin "1") (pinfunction "1_1") (pintype "passive"))
    )
    (net (code "43") (name "Net-(U$4-3V3)") (class "Default")
      (node (ref "D1") (pin "C") (pinfunction "C_C") (pintype "passive"))
      (node (ref "U$4") (pin "1") (pinfunction "3V3_1") (pintype "power_in"))
    )
    (net (code "44") (name "Net-(U$5-C)") (class "Default")
      (node (ref "R17") (pin "2") (pinfunction "2_2") (pintype "passive"))
      (node (ref "U$5") (pin "P$2") (pinfunction "C_P$2") (pintype "passive"))
    )
    (net (code "45") (name "OSCI") (class "Default")
      (node (ref "C6") (pin "1") (pinfunction "1_1") (pintype "passive"))
      (node (ref "F1") (pin "2") (pinfunction "A_2") (pintype "bidirectional"))
      (node (ref "IC3") (pin "2") (pinfunction "OSCI_2") (pintype "bidirectional"))
    )
    (net (code "46") (name "OSCO") (class "Default")
      (node (ref "C7") (pin "1") (pinfunction "1_1") (pintype "passive"))
      (node (ref "F1") (pin "1") (pinfunction "K_1") (pintype "bidirectional"))
      (node (ref "IC3") (pin "3") (pinfunction "OSCO_3") (pintype "bidirectional"))
    )
    (net (code "47") (name "PAIR_RX") (class "Default")
      (node (ref "J4") (pin "2") (pinfunction "2_2") (pintype "passive"))
      (node (ref "U2") (pin "6") (pinfunction "IO34_6") (pintype "bidirectional"))
    )
    (net (code "48") (name "PAIR_TX") (class "Default")
      (node (ref "J4") (pin "1") (pinfunction "1_1") (pintype "passive"))
      (node (ref "U2") (pin "10") (pinfunction "IO25_10") (pintype "bidirectional"))
    )
    (net (code "49") (name "PB0") (class "Default")
      (node (ref "ATTINY13A") (pin "6") (pinfunction "6_6") (pintype "passive"))
      (node (ref "IC1") (pin "5") (pinfunction "PB0_[MOSI/AIN0/OC0A/PCINT0]_5") (pintype "input"))
    )
    (net (code "50") (name "PB1") (class "Default")
      (node (ref "ATTINY13A") (pin "5") (pinfunction "5_5") (pintype "passive"))
      (node (ref "IC1") (pin "6") (pinfunction "PB1_[MISO/AIN1/OC0B/INT0/PCINT1]_6") (pintype "input"))
    )
    (net (code "51") (name "PB2") (class "Default")
      (node (ref "ATTINY13A") (pin "4") (pinfunction "4_4") (pintype "passive"))
      (node (ref "IC1") (pin "7") (pinfunction "PB2_[SCK/ADC1/T0/PCINT2]_7") (pintype "input"))
    )
    (net (code "52") (name "PB5") (class "Default")
      (node (ref "ATTINY13A") (pin "3") (pinfunction "3_3") (pintype "passive"))
      (node (ref "IC1") (pin "1") (pinfunction "PCINT5/~{RESET}/ADC0/DW]_PB5_1") (pintype "input"))
      (node (ref "R16") (pin "1") (pinfunction "1_1") (pintype "passive"))
    )
    (net (code "53") (name "PROG_RX") (class "Default")
      (node (ref "R14") (pin "1") (pinfunction "1_1") (pintype "passive"))
      (node (ref "U2") (pin "34") (pinfunction "RXD0_34") (pintype "bidirectional"))
    )
    (net (code "54") (name "PROG_TX") (class "Default")
      (node (ref "R13") (pin "1") (pinfunction "1_1") (pintype "passive"))
      (node (ref "U2") (pin "35") (pinfunction "TXD0_35") (pintype "bidirectional"))
    )
    (net (code "55") (name "PWREN") (class "Default")
      (node (ref "IC3") (pin "60") (pinfunction "PWREN#_60") (pintype "bidirectional"))
      (node (ref "R22") (pin "2") (pinfunction "2_2") (pintype "passive"))
    )
    (net (code "56") (name "PWRSAV") (class "Default")
      (node (ref "IC3") (pin "59") (pinfunction "BCBUS7_59") (pintype "bidirectional"))
    )
    (net (code "57") (name "RXD_LED") (class "Default")
      (node (ref "IC3") (pin "54") (pinfunction "BCBUS3_54") (pintype "bidirectional"))
      (node (ref "LED2") (pin "K") (pinfunction "C_K") (pintype "output"))
    )
    (net (code "58") (name "RXD_SPI_PROM_MOSI") (class "Default")
      (node (ref "IC3") (pin "39") (pinfunction "BDBUS1_39") (pintype "bidirectional"))
      (node (ref "J1") (pin "11") (pinfunction "11_11") (pintype "passive"))
      (node (ref "J2") (pin "3") (pinfunction "3_3") (pintype "passive"))
      (node (ref "R13") (pin "2") (pinfunction "2_2") (pintype "passive"))
    )
    (net (code "59") (name "SAO-GPIO1") (class "Default")
      (node (ref "U$4") (pin "3") (pinfunction "GPIO1_3") (pintype "bidirectional"))
    )
    (net (code "60") (name "SAO-GPIO2") (class "Default")
      (node (ref "U$4") (pin "6") (pinfunction "GPIO2_6") (pintype "bidirectional"))
    )
    (net (code "61") (name "SCL") (class "Default")
      (node (ref "J1") (pin "12") (pinfunction "12_12") (pintype "passive"))
      (node (ref "U$1") (pin "SCL") (pinfunction "SCL_SCL") (pintype "bidirectional"))
      (node (ref "U$4") (pin "5") (pinfunction "SCL_5") (pintype "bidirectional"))
      (node (ref "U2") (pin "36") (pinfunction "IO22_36") (pintype "bidirectional"))
    )
    (net (code "62") (name "SDA") (class "Default")
      (node (ref "J1") (pin "9") (pinfunction "9_9") (pintype "passive"))
      (node (ref "U$1") (pin "SDA") (pinfunction "SDA_SDA") (pintype "bidirectional"))
      (node (ref "U$4") (pin "2") (pinfunction "SDA_2") (pintype "bidirectional"))
      (node (ref "U2") (pin "33") (pinfunction "IO21_33") (pintype "bidirectional"))
    )
    (net (code "63") (name "SD_CS") (class "Default")
      (node (ref "J1") (pin "6") (pinfunction "6_6") (pintype "passive"))
      (node (ref "U2") (pin "29") (pinfunction "IO5_29") (pintype "bidirectional"))
    )
    (net (code "64") (name "SPI_PROM_CS") (class "Default")
      (node (ref "IC3") (pin "41") (pinfunction "BDBUS3_41") (pintype "bidirectional"))
      (node (ref "J2") (pin "1") (pinfunction "1_1") (pintype "passive"))
    )
    (net (code "65") (name "SPI_PROM_MISO") (class "Default")
      (node (ref "IC3") (pin "40") (pinfunction "BDBUS2_40") (pintype "bidirectional"))
      (node (ref "J2") (pin "2") (pinfunction "2_2") (pintype "passive"))
    )
    (net (code "66") (name "SUSPEND") (class "Default")
      (node (ref "IC3") (pin "36") (pinfunction "SUSPEND__#_36") (pintype "bidirectional"))
    )
    (net (code "67") (name "SVN") (class "Default")
      (node (ref "J4") (pin "3") (pinfunction "3_3") (pintype "passive"))
      (node (ref "U2") (pin "5") (pinfunction "SENSOR_VN_5") (pintype "bidirectional"))
    )
    (net (code "68") (name "SVP") (class "Default")
      (node (ref "J4") (pin "4") (pinfunction "4_4") (pintype "passive"))
      (node (ref "U2") (pin "4") (pinfunction "SENSOR_VP_4") (pintype "bidirectional"))
    )
    (net (code "69") (name "TOUCH_CLK") (class "Default")
      (node (ref "J8") (pin "2") (pinfunction "2_2") (pintype "passive"))
      (node (ref "U2") (pin "11") (pinfunction "IO26_11") (pintype "bidirectional"))
    )
    (net (code "70") (name "TOUCH_CS") (class "Default")
      (node (ref "J8") (pin "1") (pinfunction "1_1") (pintype "passive"))
      (node (ref "U2") (pin "12") (pinfunction "IO27_12") (pintype "bidirectional"))
    )
    (net (code "71") (name "TOUCH_DATA_IN") (class "Default")
      (node (ref "J8") (pin "6") (pinfunction "6_6") (pintype "passive"))
      (node (ref "U2") (pin "7") (pinfunction "IO35_7") (pintype "bidirectional"))
    )
    (net (code "72") (name "TOUCH_DATA_OUT") (class "Default")
      (node (ref "J8") (pin "4") (pinfunction "4_4") (pintype "passive"))
      (node (ref "U2") (pin "9") (pinfunction "IO33_9") (pintype "bidirectional"))
    )
    (net (code "73") (name "TOUCH_IRQ") (class "Default")
      (node (ref "J8") (pin "5") (pinfunction "5_5") (pintype "passive"))
      (node (ref "U2") (pin "8") (pinfunction "IO32_8") (pintype "bidirectional"))
    )
    (net (code "74") (name "TXD_LED") (class "Default")
      (node (ref "IC3") (pin "55") (pinfunction "BCBUS4_55") (pintype "bidirectional"))
      (node (ref "LED3") (pin "K") (pinfunction "C_K") (pintype "output"))
    )
    (net (code "75") (name "TXD_SPI_PROM_CLK") (class "Default")
      (node (ref "IC3") (pin "38") (pinfunction "BDBUS0_38") (pintype "bidirectional"))
      (node (ref "J1") (pin "10") (pinfunction "10_10") (pintype "passive"))
      (node (ref "J2") (pin "4") (pinfunction "4_4") (pintype "passive"))
      (node (ref "R14") (pin "2") (pinfunction "2_2") (pintype "passive"))
    )
    (net (code "76") (name "USB_DM") (class "Default")
      (node (ref "IC3") (pin "7") (pinfunction "DM_7") (pintype "bidirectional"))
      (node (ref "U$2") (pin "D-") (pinfunction "D-_D-") (pintype "bidirectional"))
    )
    (net (code "77") (name "USB_DP") (class "Default")
      (node (ref "IC3") (pin "8") (pinfunction "DP_8") (pintype "bidirectional"))
      (node (ref "U$2") (pin "D+") (pinfunction "D+_D+") (pintype "bidirectional"))
    )
    (net (code "78") (name "VBAT") (class "Default")
      (node (ref "C26") (pin "1") (pinfunction "1_1") (pintype "passive"))
      (node (ref "C27") (pin "1") (pinfunction "1_1") (pintype "passive"))
      (node (ref "C28") (pin "1") (pinfunction "1_1") (pintype "passive"))
      (node (ref "C29") (pin "1") (pinfunction "1_1") (pintype "passive"))
      (node (ref "C32") (pin "1") (pinfunction "1_1") (pintype "passive"))
      (node (ref "C33") (pin "1") (pinfunction "1_1") (pintype "passive"))
      (node (ref "C4") (pin "1") (pinfunction "1_1") (pintype "passive"))
      (node (ref "IC1") (pin "8") (pinfunction "VCC_8") (pintype "power_in"))
      (node (ref "IC2") (pin "4") (pinfunction "VIN_4") (pintype "bidirectional"))
      (node (ref "IC5") (pin "1") (pinfunction "VDD_1") (pintype "power_in"))
      (node (ref "IC6") (pin "1") (pinfunction "VDD_1") (pintype "power_in"))
      (node (ref "IC7") (pin "1") (pinfunction "VDD_1") (pintype "power_in"))
      (node (ref "IC8") (pin "1") (pinfunction "VDD_1") (pintype "power_in"))
      (node (ref "OFF/ON") (pin "3") (pinfunction "S_3") (pintype "passive"))
      (node (ref "R16") (pin "2") (pinfunction "2_2") (pintype "passive"))
      (node (ref "RESETTABLE_FUSE") (pin "2") (pinfunction "2_2") (pintype "passive"))
    )
    (net (code "79") (name "VCC") (class "Default")
      (node (ref "C1") (pin "1") (pinfunction "1_1") (pintype "passive"))
      (node (ref "C11") (pin "1") (pinfunction "1_1") (pintype "passive"))
      (node (ref "C14") (pin "1") (pinfunction "1_1") (pintype "passive"))
      (node (ref "C15") (pin "1") (pinfunction "1_1") (pintype "passive"))
      (node (ref "C16") (pin "1") (pinfunction "1_1") (pintype "passive"))
      (node (ref "C3") (pin "1") (pinfunction "1_1") (pintype "passive"))
      (node (ref "C35") (pin "1") (pinfunction "1_1") (pintype "passive"))
      (node (ref "C5") (pin "1") (pinfunction "1_1") (pintype "passive"))
      (node (ref "C8") (pin "1") (pinfunction "1_1") (pintype "passive"))
      (node (ref "D1") (pin "A") (pinfunction "A_A") (pintype "passive"))
      (node (ref "EMIFILTER1") (pin "1") (pinfunction "IN/OUT_1") (pintype "bidirectional"))
      (node (ref "EMIFILTER2") (pin "1") (pinfunction "IN/OUT_1") (pintype "bidirectional"))
      (node (ref "IC2") (pin "1") (pinfunction "VOUT_1") (pintype "bidirectional"))
      (node (ref "IC3") (pin "20") (pinfunction "VCCIO_1_20") (pintype "bidirectional"))
      (node (ref "IC3") (pin "31") (pinfunction "VCCIO_2_31") (pintype "bidirectional"))
      (node (ref "IC3") (pin "42") (pinfunction "VCCIO_3_42") (pintype "bidirectional"))
      (node (ref "IC3") (pin "50") (pinfunction "VREGIN_50") (pintype "bidirectional"))
      (node (ref "IC3") (pin "56") (pinfunction "VCCIO_4_56") (pintype "bidirectional"))
      (node (ref "IC4") (pin "6") (pinfunction "VCC_6") (pintype "power_in"))
      (node (ref "J1") (pin "1") (pinfunction "1_1") (pintype "passive"))
      (node (ref "J2") (pin "6") (pinfunction "6_6") (pintype "passive"))
      (node (ref "R1") (pin "2") (pinfunction "2_2") (pintype "passive"))
      (node (ref "R11") (pin "2") (pinfunction "2_2") (pintype "passive"))
      (node (ref "R12") (pin "2") (pinfunction "2_2") (pintype "passive"))
      (node (ref "R15") (pin "1") (pinfunction "1_1") (pintype "passive"))
      (node (ref "R18") (pin "1") (pinfunction "1_1") (pintype "passive"))
      (node (ref "R4") (pin "2") (pinfunction "2_2") (pintype "passive"))
      (node (ref "R5") (pin "1") (pinfunction "1_1") (pintype "passive"))
      (node (ref "R7") (pin "2") (pinfunction "2_2") (pintype "passive"))
      (node (ref "R8") (pin "1") (pinfunction "1_1") (pintype "passive"))
      (node (ref "R9") (pin "2") (pinfunction "2_2") (pintype "passive"))
      (node (ref "U$1") (pin "VCC") (pinfunction "VCC_VCC") (pintype "power_in"))
      (node (ref "U2") (pin "2") (pinfunction "3V3_2") (pintype "bidirectional"))
    )
    (net (code "80") (name "VCC1.8") (class "Default")
      (node (ref "C10") (pin "1") (pinfunction "1_1") (pintype "passive"))
      (node (ref "C12") (pin "1") (pinfunction "1_1") (pintype "passive"))
      (node (ref "C17") (pin "1") (pinfunction "1_1") (pintype "passive"))
      (node (ref "C9") (pin "1") (pinfunction "1_1") (pintype "passive"))
      (node (ref "IC3") (pin "12") (pinfunction "VCORE_1_12") (pintype "bidirectional"))
      (node (ref "IC3") (pin "37") (pinfunction "VCORE_2_37") (pintype "bidirectional"))
      (node (ref "IC3") (pin "49") (pinfunction "VREGOUT_49") (pintype "bidirectional"))
      (node (ref "IC3") (pin "64") (pinfunction "VCORE_3_64") (pintype "bidirectional"))
    )
    (net (code "81") (name "VCC5V") (class "Default")
      (node (ref "C13") (pin "2") (pinfunction "2_2") (pintype "passive"))
      (node (ref "IC-IP5305") (pin "VIN") (pinfunction "1_VIN") (pintype "power_in"))
      (node (ref "R2") (pin "1") (pinfunction "1_1") (pintype "passive"))
      (node (ref "U$2") (pin "+5V") (pinfunction "+5V_+5V") (pintype "bidirectional"))
    )
    (net (code "82") (name "unconnected-(IC2-ADJ-Pad8)") (class "Default")
      (node (ref "IC2") (pin "8") (pinfunction "ADJ_8") (pintype "bidirectional"))
    )
    (net (code "83") (name "unconnected-(IC3-ACBUS0-Pad26)") (class "Default")
      (node (ref "IC3") (pin "26") (pinfunction "ACBUS0_26") (pintype "bidirectional"))
    )
    (net (code "84") (name "unconnected-(IC3-ACBUS1-Pad27)") (class "Default")
      (node (ref "IC3") (pin "27") (pinfunction "ACBUS1_27") (pintype "bidirectional"))
    )
    (net (code "85") (name "unconnected-(IC3-ACBUS2-Pad28)") (class "Default")
      (node (ref "IC3") (pin "28") (pinfunction "ACBUS2_28") (pintype "bidirectional"))
    )
    (net (code "86") (name "unconnected-(IC3-ACBUS3-Pad29)") (class "Default")
      (node (ref "IC3") (pin "29") (pinfunction "ACBUS3_29") (pintype "bidirectional"))
    )
    (net (code "87") (name "unconnected-(IC3-ACBUS4-Pad30)") (class "Default")
      (node (ref "IC3") (pin "30") (pinfunction "ACBUS4_30") (pintype "bidirectional"))
    )
    (net (code "88") (name "unconnected-(IC3-ACBUS5-Pad32)") (class "Default")
      (node (ref "IC3") (pin "32") (pinfunction "ACBUS5_32") (pintype "bidirectional"))
    )
    (net (code "89") (name "unconnected-(IC3-ACBUS6-Pad33)") (class "Default")
      (node (ref "IC3") (pin "33") (pinfunction "ACBUS6_33") (pintype "bidirectional"))
    )
    (net (code "90") (name "unconnected-(IC3-ACBUS7-Pad34)") (class "Default")
      (node (ref "IC3") (pin "34") (pinfunction "ACBUS7_34") (pintype "bidirectional"))
    )
    (net (code "91") (name "unconnected-(IC3-ADBUS4-Pad21)") (class "Default")
      (node (ref "IC3") (pin "21") (pinfunction "ADBUS4_21") (pintype "bidirectional"))
    )
    (net (code "92") (name "unconnected-(IC3-ADBUS5-Pad22)") (class "Default")
      (node (ref "IC3") (pin "22") (pinfunction "ADBUS5_22") (pintype "bidirectional"))
    )
    (net (code "93") (name "unconnected-(IC3-ADBUS6-Pad23)") (class "Default")
      (node (ref "IC3") (pin "23") (pinfunction "ADBUS6_23") (pintype "bidirectional"))
    )
    (net (code "94") (name "unconnected-(IC3-ADBUS7-Pad24)") (class "Default")
      (node (ref "IC3") (pin "24") (pinfunction "ADBUS7_24") (pintype "bidirectional"))
    )
    (net (code "95") (name "unconnected-(IC3-BCBUS0-Pad48)") (class "Default")
      (node (ref "IC3") (pin "48") (pinfunction "BCBUS0_48") (pintype "bidirectional"))
    )
    (net (code "96") (name "unconnected-(IC3-BCBUS1-Pad52)") (class "Default")
      (node (ref "IC3") (pin "52") (pinfunction "BCBUS1_52") (pintype "bidirectional"))
    )
    (net (code "97") (name "unconnected-(IC3-BCBUS2-Pad53)") (class "Default")
      (node (ref "IC3") (pin "53") (pinfunction "BCBUS2_53") (pintype "bidirectional"))
    )
    (net (code "98") (name "unconnected-(IC3-BCBUS5-Pad57)") (class "Default")
      (node (ref "IC3") (pin "57") (pinfunction "BCBUS5_57") (pintype "bidirectional"))
    )
    (net (code "99") (name "unconnected-(IC3-BCBUS6-Pad58)") (class "Default")
      (node (ref "IC3") (pin "58") (pinfunction "BCBUS6_58") (pintype "bidirectional"))
    )
    (net (code "100") (name "unconnected-(IC3-BDBUS4-Pad43)") (class "Default")
      (node (ref "IC3") (pin "43") (pinfunction "BDBUS4_43") (pintype "bidirectional"))
    )
    (net (code "101") (name "unconnected-(IC3-BDBUS5-Pad44)") (class "Default")
      (node (ref "IC3") (pin "44") (pinfunction "BDBUS5_44") (pintype "bidirectional"))
    )
    (net (code "102") (name "unconnected-(IC3-BDBUS6-Pad45)") (class "Default")
      (node (ref "IC3") (pin "45") (pinfunction "BDBUS6_45") (pintype "bidirectional"))
    )
    (net (code "103") (name "unconnected-(IC3-BDBUS7-Pad46)") (class "Default")
      (node (ref "IC3") (pin "46") (pinfunction "BDBUS7_46") (pintype "bidirectional"))
    )
    (net (code "104") (name "unconnected-(IC8-DOUT-Pad2)") (class "Default")
      (node (ref "IC8") (pin "2") (pinfunction "DOUT_2") (pintype "output"))
    )
    (net (code "105") (name "unconnected-(U$1-NC_1-PadNC1)") (class "Default")
      (node (ref "U$1") (pin "NC1") (pinfunction "NC_1_NC1") (pintype "no_connect"))
    )
    (net (code "106") (name "unconnected-(U$1-NC_2-PadNC2)") (class "Default")
      (node (ref "U$1") (pin "NC2") (pinfunction "NC_2_NC2") (pintype "no_connect"))
    )
    (net (code "107") (name "unconnected-(U$1-NC_3-PadNC3)") (class "Default")
      (node (ref "U$1") (pin "NC3") (pinfunction "NC_3_NC3") (pintype "no_connect"))
    )
    (net (code "108") (name "unconnected-(U$1-NC_4-PadNC4)") (class "Default")
      (node (ref "U$1") (pin "NC4") (pinfunction "NC_4_NC4") (pintype "no_connect"))
    )
    (net (code "109") (name "unconnected-(U$2-PadID)") (class "Default")
      (node (ref "U$2") (pin "ID") (pinfunction "ID_ID") (pintype "bidirectional"))
    )
    (net (code "110") (name "unconnected-(U2-CLK-Pad20)") (class "Default")
      (node (ref "U2") (pin "20") (pinfunction "CLK_20") (pintype "bidirectional"))
    )
    (net (code "111") (name "unconnected-(U2-CMD-Pad19)") (class "Default")
      (node (ref "U2") (pin "19") (pinfunction "CMD_19") (pintype "bidirectional"))
    )
    (net (code "112") (name "unconnected-(U2-NC-Pad32)") (class "Default")
      (node (ref "U2") (pin "32") (pinfunction "NC_32") (pintype "bidirectional"))
    )
    (net (code "113") (name "unconnected-(U2-SD1-Pad22)") (class "Default")
      (node (ref "U2") (pin "22") (pinfunction "SD1_22") (pintype "bidirectional"))
    )
    (net (code "114") (name "unconnected-(U2-SD2-Pad17)") (class "Default")
      (node (ref "U2") (pin "17") (pinfunction "SD2_17") (pintype "bidirectional"))
    )
    (net (code "115") (name "unconnected-(U2-SD3-Pad18)") (class "Default")
      (node (ref "U2") (pin "18") (pinfunction "SD3_18") (pintype "bidirectional"))
    )
    (net (code "116") (name "unconnected-(U2-SDO-Pad21)") (class "Default")
      (node (ref "U2") (pin "21") (pinfunction "SDO_21") (pintype "bidirectional"))
    )
  )
)
